# IO_Connector.net
KiCad netlist of a schematic drawn in Altium Designer
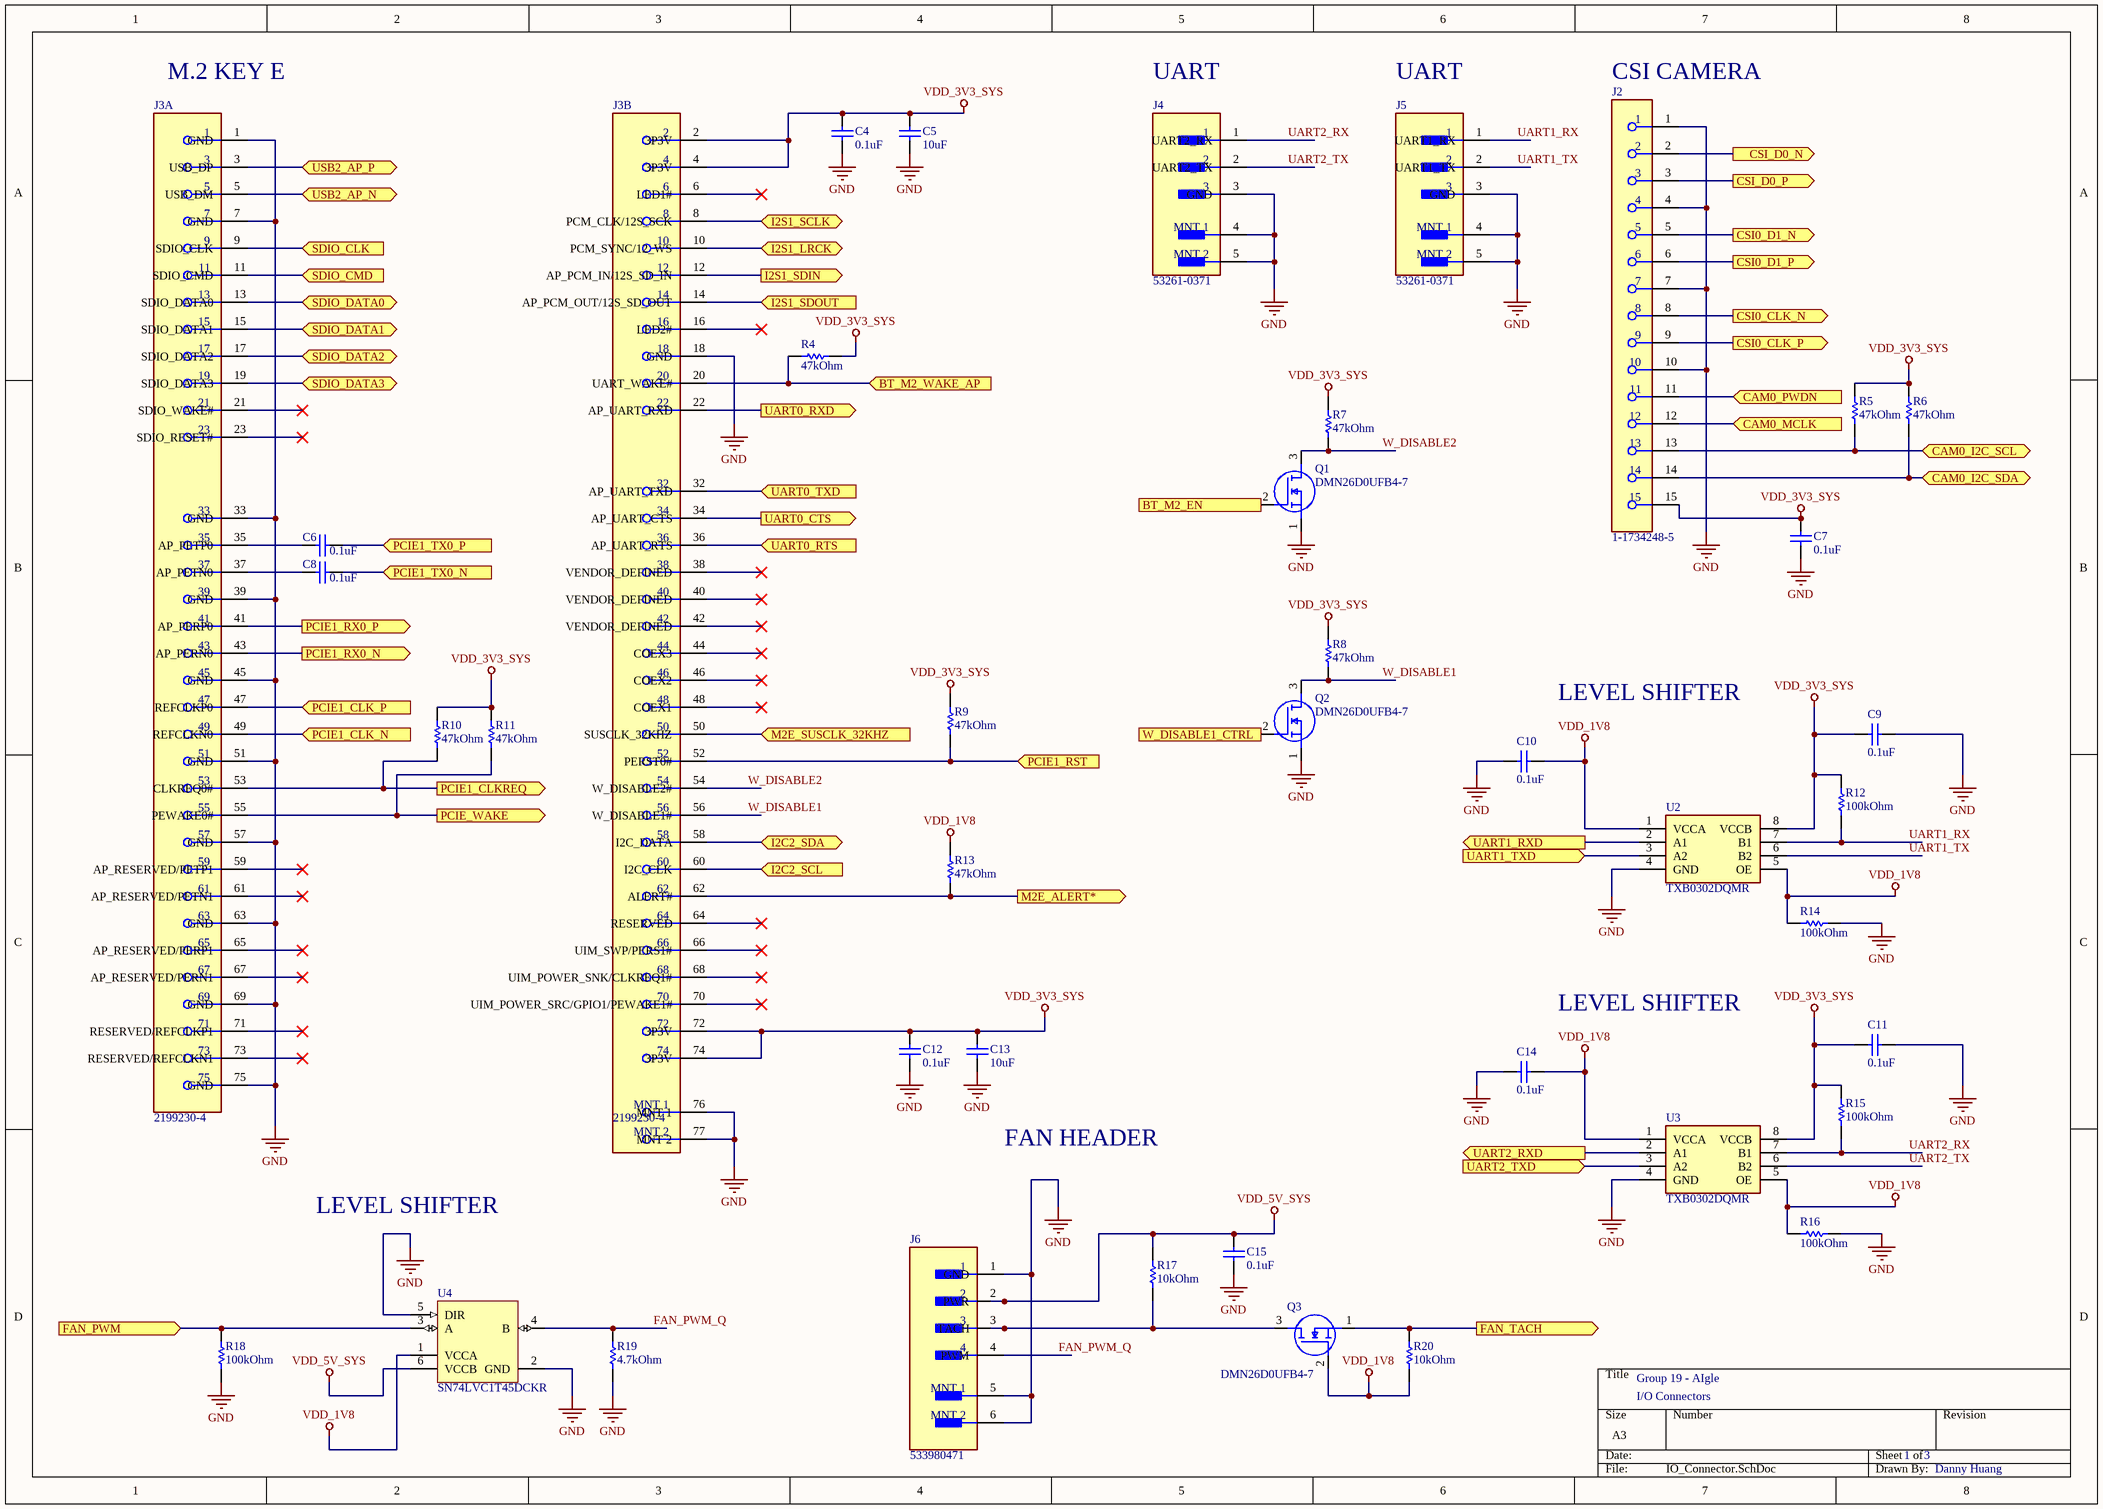
[diagram p0: IO_Connector.SchDoc]

(export (version "E")
  (design (tool "Eeschema 10.0.6"))
  (components
    (comp (ref "C4")
      (value "0.1uF")
      (footprint "CAPC1005X55X30NL05T10")
      (fields (field (name "MANUFACTURER") "Kemet") (field (name "PART NUMBER") "C0402C104K9RACTU"))
      (libsource (lib "Altium Content Vault") (part "CAP"))
    )
    (comp (ref "C5")
      (value "10uF")
      (footprint "CAPC1608X90X35NL10T15")
      (fields (field (name "PART NUMBER") "GRM188R60J106ME47D") (field (name "MANUFACTURER") "Murata"))
      (libsource (lib "Altium Content Vault") (part "CAP"))
    )
    (comp (ref "C6")
      (value "0.1uF")
      (footprint "CAPC1005X55X30NL05T10")
      (fields (field (name "MANUFACTURER") "Kemet") (field (name "PART NUMBER") "C0402C104K9RACTU"))
      (libsource (lib "Altium Content Vault") (part "CAP"))
    )
    (comp (ref "C7")
      (value "0.1uF")
      (footprint "CAPC1005X55X30NL05T10")
      (fields (field (name "MANUFACTURER") "Kemet") (field (name "PART NUMBER") "C0402C104K9RACTU"))
      (libsource (lib "Altium Content Vault") (part "CAP"))
    )
    (comp (ref "C8")
      (value "0.1uF")
      (footprint "CAPC1005X55X30NL05T10")
      (fields (field (name "MANUFACTURER") "Kemet") (field (name "PART NUMBER") "C0402C104K9RACTU"))
      (libsource (lib "Altium Content Vault") (part "CAP"))
    )
    (comp (ref "C9")
      (value "0.1uF")
      (footprint "CAPC1005X55X30NL05T10")
      (fields (field (name "MANUFACTURER") "Kemet") (field (name "PART NUMBER") "C0402C104K9RACTU"))
      (libsource (lib "Altium Content Vault") (part "CAP"))
    )
    (comp (ref "C10")
      (value "0.1uF")
      (footprint "CAPC1005X55X30NL05T10")
      (fields (field (name "MANUFACTURER") "Kemet") (field (name "PART NUMBER") "C0402C104K9RACTU"))
      (libsource (lib "Altium Content Vault") (part "CAP"))
    )
    (comp (ref "C11")
      (value "0.1uF")
      (footprint "CAPC1005X55X30NL05T10")
      (fields (field (name "MANUFACTURER") "Kemet") (field (name "PART NUMBER") "C0402C104K9RACTU"))
      (libsource (lib "Altium Content Vault") (part "CAP"))
    )
    (comp (ref "C12")
      (value "0.1uF")
      (footprint "CAPC1005X55X30NL05T10")
      (fields (field (name "MANUFACTURER") "Kemet") (field (name "PART NUMBER") "C0402C104K9RACTU"))
      (libsource (lib "Altium Content Vault") (part "CAP"))
    )
    (comp (ref "C13")
      (value "10uF")
      (footprint "CAPC1608X90X35NL10T15")
      (fields (field (name "PART NUMBER") "GRM188R60J106ME47D") (field (name "MANUFACTURER") "Murata"))
      (libsource (lib "Altium Content Vault") (part "CAP"))
    )
    (comp (ref "C14")
      (value "0.1uF")
      (footprint "CAPC1005X55X30NL05T10")
      (fields (field (name "MANUFACTURER") "Kemet") (field (name "PART NUMBER") "C0402C104K9RACTU"))
      (libsource (lib "Altium Content Vault") (part "CAP"))
    )
    (comp (ref "C15")
      (value "0.1uF")
      (footprint "CAPC1005X55X30NL05T10")
      (fields (field (name "MANUFACTURER") "Kemet") (field (name "PART NUMBER") "C0402C104K9RACTU"))
      (libsource (lib "Altium Content Vault") (part "CAP"))
    )
    (comp (ref "J2")
      (value "1-1734248-5")
      (footprint "FP-1-1734248-5-MFG")
      (description "CONN FPC VERT 15POS 1.00MM SMD")
      (fields
        (field (name "MANUFACTURER") "TE")
        (field (name "OCTOPART") "https://octopart.com/1-1734248-5-te+connectivity-40620898")
      )
      (libsource (lib "Altium Content Vault") (part "a0777be16b290adccad2a8f9338c195"))
    )
    (comp (ref "J3")
      (value "2199230-4")
      (footprint "FP-2199230-4-MFG")
      (description "CONN FEMALE 67POS 0.020 GOLD")
      (fields
        (field (name "MANUFACTURER") "TE Connectivity")
        (field (name "OCTOPART") "https://octopart.com/2199230-4-te+connectivity-46436156")
      )
      (libsource (lib "Altium Content Vault") (part "6b4bc9aaecd91677fa565b830470f16"))
    )
    (comp (ref "J4")
      (value "53261-0371")
      (footprint "FP-53261-0371-MFG")
      (description "CONN HEADER SMD R/A 3POS 1.25MM")
      (fields
        (field (name "MANUFACTURER") "Molex")
        (field (name "OCTOPART") "https://octopart.com/53261-0371-molex-655314")
      )
      (libsource (lib "Altium Content Vault") (part "13850a6865a90496d8e6d51657cef87"))
    )
    (comp (ref "J5")
      (value "53261-0371")
      (footprint "FP-53261-0371-MFG")
      (description "CONN HEADER SMD R/A 3POS 1.25MM")
      (fields
        (field (name "MANUFACTURER") "Molex")
        (field (name "OCTOPART") "https://octopart.com/53261-0371-molex-655314")
      )
      (libsource (lib "Altium Content Vault") (part "13850a6865a90496d8e6d51657cef87"))
    )
    (comp (ref "J6")
      (value "533980471")
      (footprint "FP-533980471-MFG")
      (description "CONN HEADER SMD 4POS 1.25MM")
      (fields
        (field (name "OCTOPART") "https://octopart.com/53398-0471-molex-655296")
        (field (name "MANUFACTURER") "Molex")
      )
      (libsource (lib "Altium Content Vault") (part "3b6f738a5616415d78381ad43816e4a"))
    )
    (comp (ref "Q1")
      (value "DMN26D0UFB4-7")
      (footprint "SamacSys:DMN26D0UFB47")
      (description "MOSFET (N-Channel)")
      (fields (field (name "MOUSER PART NUMBER") "621-DMN26D0UFB4-7"))
      (libsource (lib "*") (part "DMN26D0UFB4-7"))
    )
    (comp (ref "Q2")
      (value "DMN26D0UFB4-7")
      (footprint "SamacSys:DMN26D0UFB47")
      (description "MOSFET (N-Channel)")
      (fields (field (name "MOUSER PART NUMBER") "621-DMN26D0UFB4-7"))
      (libsource (lib "*") (part "DMN26D0UFB4-7"))
    )
    (comp (ref "Q3")
      (value "DMN26D0UFB4-7")
      (footprint "SamacSys:DMN26D0UFB47")
      (description "MOSFET (N-Channel)")
      (fields (field (name "MOUSER PART NUMBER") "621-DMN26D0UFB4-7"))
      (libsource (lib "*") (part "DMN26D0UFB4-7"))
    )
    (comp (ref "R4")
      (value "47kOhm")
      (footprint "RESC1005X40X25LL05T05")
      (fields (field (name "MANUFACTURER") "Vishay Dale") (field (name "PART NUMBER") "CRCW040247K0JNED"))
      (libsource (lib "Altium Content Vault") (part "RES"))
    )
    (comp (ref "R5")
      (value "47kOhm")
      (footprint "RESC1005X40X25LL05T05")
      (fields (field (name "MANUFACTURER") "Vishay Dale") (field (name "PART NUMBER") "CRCW040247K0JNED"))
      (libsource (lib "Altium Content Vault") (part "RES"))
    )
    (comp (ref "R6")
      (value "47kOhm")
      (footprint "RESC1005X40X25LL05T05")
      (fields (field (name "MANUFACTURER") "Vishay Dale") (field (name "PART NUMBER") "CRCW040247K0JNED"))
      (libsource (lib "Altium Content Vault") (part "RES"))
    )
    (comp (ref "R7")
      (value "47kOhm")
      (footprint "RESC1005X40X25LL05T05")
      (fields (field (name "MANUFACTURER") "Vishay Dale") (field (name "PART NUMBER") "CRCW040247K0JNED"))
      (libsource (lib "Altium Content Vault") (part "RES"))
    )
    (comp (ref "R8")
      (value "47kOhm")
      (footprint "RESC1005X40X25LL05T05")
      (fields (field (name "MANUFACTURER") "Vishay Dale") (field (name "PART NUMBER") "CRCW040247K0JNED"))
      (libsource (lib "Altium Content Vault") (part "RES"))
    )
    (comp (ref "R9")
      (value "47kOhm")
      (footprint "RESC1005X40X25LL05T05")
      (fields (field (name "MANUFACTURER") "Vishay Dale") (field (name "PART NUMBER") "CRCW040247K0JNED"))
      (libsource (lib "Altium Content Vault") (part "RES"))
    )
    (comp (ref "R10")
      (value "47kOhm")
      (footprint "RESC1005X40X25LL05T05")
      (fields (field (name "MANUFACTURER") "Vishay Dale") (field (name "PART NUMBER") "CRCW040247K0JNED"))
      (libsource (lib "Altium Content Vault") (part "RES"))
    )
    (comp (ref "R11")
      (value "47kOhm")
      (footprint "RESC1005X40X25LL05T05")
      (fields (field (name "MANUFACTURER") "Vishay Dale") (field (name "PART NUMBER") "CRCW040247K0JNED"))
      (libsource (lib "Altium Content Vault") (part "RES"))
    )
    (comp (ref "R12")
      (value "100kOhm")
      (footprint "RESC1005X40X25ML05T05")
      (description "Chip Resistor, 100 KOhm, +/- 1%, 0.63 W, -55 to 155 degC, 0402 (1005 Metric), RoHS, Tape and Reel")
      (fields (field (name "TOLERANCE") "1%"))
      (libsource (lib "Altium Content Vault") (part "RES-2"))
    )
    (comp (ref "R13")
      (value "47kOhm")
      (footprint "RESC1005X40X25LL05T05")
      (fields (field (name "MANUFACTURER") "Vishay Dale") (field (name "PART NUMBER") "CRCW040247K0JNED"))
      (libsource (lib "Altium Content Vault") (part "RES"))
    )
    (comp (ref "R14")
      (value "100kOhm")
      (footprint "RESC1005X40X25ML05T05")
      (description "Chip Resistor, 100 KOhm, +/- 1%, 0.63 W, -55 to 155 degC, 0402 (1005 Metric), RoHS, Tape and Reel")
      (fields (field (name "TOLERANCE") "1%"))
      (libsource (lib "Altium Content Vault") (part "RES-2"))
    )
    (comp (ref "R15")
      (value "100kOhm")
      (footprint "RESC1005X40X25ML05T05")
      (description "Chip Resistor, 100 KOhm, +/- 1%, 0.63 W, -55 to 155 degC, 0402 (1005 Metric), RoHS, Tape and Reel")
      (fields (field (name "TOLERANCE") "1%"))
      (libsource (lib "Altium Content Vault") (part "RES-2"))
    )
    (comp (ref "R16")
      (value "100kOhm")
      (footprint "RESC1005X40X25ML05T05")
      (description "Chip Resistor, 100 KOhm, +/- 1%, 0.63 W, -55 to 155 degC, 0402 (1005 Metric), RoHS, Tape and Reel")
      (fields (field (name "TOLERANCE") "1%"))
      (libsource (lib "Altium Content Vault") (part "RES-2"))
    )
    (comp (ref "R17")
      (value "10kOhm")
      (footprint "RESC1005X40X25NL05T05")
      (fields (field (name "MANUFACTURER") "Vishay Dale") (field (name "PART NUMBER") "CRCW040210K0JNED"))
      (libsource (lib "Altium Content Vault") (part "RES"))
    )
    (comp (ref "R18")
      (value "100kOhm")
      (footprint "RESC1005X40X25ML05T05")
      (description "Chip Resistor, 100 KOhm, +/- 1%, 0.63 W, -55 to 155 degC, 0402 (1005 Metric), RoHS, Tape and Reel")
      (fields (field (name "TOLERANCE") "1%"))
      (libsource (lib "Altium Content Vault") (part "RES-2"))
    )
    (comp (ref "R19")
      (value "4.7kOhm")
      (footprint "RESC1005X40X25ML05T05")
      (fields
        (field (name "PART NUMBER") "CRCW04024K70JNED")
        (field (name "MANUFACTURER") "Vishay BCcomponents")
      )
      (libsource (lib "Altium Content Vault") (part "RES"))
    )
    (comp (ref "R20")
      (value "10kOhm")
      (footprint "RESC1005X40X25NL05T05")
      (fields (field (name "MANUFACTURER") "Vishay Dale") (field (name "PART NUMBER") "CRCW040210K0JNED"))
      (libsource (lib "Altium Content Vault") (part "RES"))
    )
    (comp (ref "U2")
      (value "TXB0302DQMR")
      (footprint "SamacSys:SON40P120X180X40-8N")
      (description "Integrated Circuit")
      (fields (field (name "MOUSER PART NUMBER") "595-TXB0302DQMR"))
      (libsource (lib "*") (part "TXB0302DQMR"))
    )
    (comp (ref "U3")
      (value "TXB0302DQMR")
      (footprint "SamacSys:SON40P120X180X40-8N")
      (description "Integrated Circuit")
      (fields (field (name "MOUSER PART NUMBER") "595-TXB0302DQMR"))
      (libsource (lib "*") (part "TXB0302DQMR"))
    )
    (comp (ref "U4")
      (value "SN74LVC1T45DCKR")
      (footprint "DCK0006A_L")
      (fields
        (field (name "MANUFACTURER") "Texas Instruments")
        (field (name "GENERIC PART NUMBER") "SN74LVC1T45")
      )
      (libsource (lib "Altium Content Vault") (part "TI-SN74XVC1T45-6"))
    )
  )
  (nets
    (net (code "1") (name "/BT_M2_EN") (class "Default")
      (node (ref "Q1") (pin "2") (pinfunction "G_2") (pintype "passive"))
    )
    (net (code "2") (name "/BT_M2_WAKE_AP") (class "Default")
      (node (ref "J3") (pin "20") (pinfunction "20_20") (pintype "passive"))
      (node (ref "R4") (pin "2") (pinfunction "2_2") (pintype "passive"))
    )
    (net (code "3") (name "/CAM0_I2C_SCL") (class "Default")
      (node (ref "J2") (pin "13") (pinfunction "13_13") (pintype "passive"))
      (node (ref "R5") (pin "1") (pinfunction "1_1") (pintype "passive"))
    )
    (net (code "4") (name "/CAM0_I2C_SDA") (class "Default")
      (node (ref "J2") (pin "14") (pinfunction "14_14") (pintype "passive"))
      (node (ref "R6") (pin "1") (pinfunction "1_1") (pintype "passive"))
    )
    (net (code "5") (name "/CAM0_MCLK") (class "Default")
      (node (ref "J2") (pin "12") (pinfunction "12_12") (pintype "passive"))
    )
    (net (code "6") (name "/CAM0_PWDN") (class "Default")
      (node (ref "J2") (pin "11") (pinfunction "11_11") (pintype "passive"))
    )
    (net (code "7") (name "/CSI0_CLK_N") (class "Default")
      (node (ref "J2") (pin "8") (pinfunction "8_8") (pintype "passive"))
    )
    (net (code "8") (name "/CSI0_CLK_P") (class "Default")
      (node (ref "J2") (pin "9") (pinfunction "9_9") (pintype "passive"))
    )
    (net (code "9") (name "/CSI0_D1_N") (class "Default")
      (node (ref "J2") (pin "5") (pinfunction "5_5") (pintype "passive"))
    )
    (net (code "10") (name "/CSI0_D1_P") (class "Default")
      (node (ref "J2") (pin "6") (pinfunction "6_6") (pintype "passive"))
    )
    (net (code "11") (name "/CSI_D0_N") (class "Default")
      (node (ref "J2") (pin "2") (pinfunction "2_2") (pintype "passive"))
    )
    (net (code "12") (name "/CSI_D0_P") (class "Default")
      (node (ref "J2") (pin "3") (pinfunction "3_3") (pintype "passive"))
    )
    (net (code "13") (name "/FAN_PWM") (class "Default")
      (node (ref "R18") (pin "1") (pinfunction "1_1") (pintype "passive"))
      (node (ref "U4") (pin "3") (pinfunction "A_3") (pintype "bidirectional"))
    )
    (net (code "14") (name "/FAN_PWM_Q") (class "Default")
      (node (ref "J6") (pin "4") (pinfunction "PWM_4") (pintype "passive"))
      (node (ref "R19") (pin "2") (pinfunction "2_2") (pintype "passive"))
      (node (ref "U4") (pin "4") (pinfunction "B_4") (pintype "bidirectional"))
    )
    (net (code "15") (name "/FAN_TACH") (class "Default")
      (node (ref "Q3") (pin "1") (pinfunction "S_1") (pintype "passive"))
      (node (ref "R20") (pin "2") (pinfunction "2_2") (pintype "passive"))
    )
    (net (code "16") (name "/I2C2_SCL") (class "Default")
      (node (ref "J3") (pin "60") (pinfunction "60_60") (pintype "passive"))
    )
    (net (code "17") (name "/I2C2_SDA") (class "Default")
      (node (ref "J3") (pin "58") (pinfunction "58_58") (pintype "passive"))
    )
    (net (code "18") (name "/I2S1_LRCK") (class "Default")
      (node (ref "J3") (pin "10") (pinfunction "10_10") (pintype "passive"))
    )
    (net (code "19") (name "/I2S1_SCLK") (class "Default")
      (node (ref "J3") (pin "8") (pinfunction "8_8") (pintype "passive"))
    )
    (net (code "20") (name "/I2S1_SDIN") (class "Default")
      (node (ref "J3") (pin "12") (pinfunction "12_12") (pintype "passive"))
    )
    (net (code "21") (name "/I2S1_SDOUT") (class "Default")
      (node (ref "J3") (pin "14") (pinfunction "14_14") (pintype "passive"))
    )
    (net (code "22") (name "/M2E_ALERT*") (class "Default")
      (node (ref "J3") (pin "62") (pinfunction "62_62") (pintype "passive"))
      (node (ref "R13") (pin "1") (pinfunction "1_1") (pintype "passive"))
    )
    (net (code "23") (name "/M2E_SUSCLK_32KHZ") (class "Default")
      (node (ref "J3") (pin "50") (pinfunction "50_50") (pintype "passive"))
    )
    (net (code "24") (name "/PCIE1_CLKREQ") (class "Default")
      (node (ref "J3") (pin "53") (pinfunction "CLKREQ0#_53") (pintype "passive"))
      (node (ref "R10") (pin "1") (pinfunction "1_1") (pintype "passive"))
    )
    (net (code "25") (name "/PCIE1_CLK_N") (class "Default")
      (node (ref "J3") (pin "49") (pinfunction "REFCLKN0_49") (pintype "passive"))
    )
    (net (code "26") (name "/PCIE1_CLK_P") (class "Default")
      (node (ref "J3") (pin "47") (pinfunction "REFCLKP0_47") (pintype "passive"))
    )
    (net (code "27") (name "/PCIE1_RST") (class "Default")
      (node (ref "J3") (pin "52") (pinfunction "52_52") (pintype "passive"))
      (node (ref "R9") (pin "1") (pinfunction "1_1") (pintype "passive"))
    )
    (net (code "28") (name "/PCIE1_RX0_N") (class "Default")
      (node (ref "J3") (pin "43") (pinfunction "AP_PERN0_43") (pintype "passive"))
    )
    (net (code "29") (name "/PCIE1_RX0_P") (class "Default")
      (node (ref "J3") (pin "41") (pinfunction "AP_PERP0_41") (pintype "passive"))
    )
    (net (code "30") (name "/PCIE1_TX0_N") (class "Default")
      (node (ref "C8") (pin "1") (pinfunction "1_1") (pintype "passive"))
    )
    (net (code "31") (name "/PCIE1_TX0_P") (class "Default")
      (node (ref "C6") (pin "1") (pinfunction "1_1") (pintype "passive"))
    )
    (net (code "32") (name "/PCIE_WAKE") (class "Default")
      (node (ref "J3") (pin "55") (pinfunction "PEWAKE0#_55") (pintype "passive"))
      (node (ref "R11") (pin "1") (pinfunction "1_1") (pintype "passive"))
    )
    (net (code "33") (name "/SDIO_CLK") (class "Default")
      (node (ref "J3") (pin "9") (pinfunction "SDIO_CLK_9") (pintype "passive"))
    )
    (net (code "34") (name "/SDIO_CMD") (class "Default")
      (node (ref "J3") (pin "11") (pinfunction "SDIO_CMD_11") (pintype "passive"))
    )
    (net (code "35") (name "/SDIO_DATA0") (class "Default")
      (node (ref "J3") (pin "13") (pinfunction "SDIO_DATA0_13") (pintype "passive"))
    )
    (net (code "36") (name "/SDIO_DATA1") (class "Default")
      (node (ref "J3") (pin "15") (pinfunction "SDIO_DATA1_15") (pintype "passive"))
    )
    (net (code "37") (name "/SDIO_DATA2") (class "Default")
      (node (ref "J3") (pin "17") (pinfunction "SDIO_DATA2_17") (pintype "passive"))
    )
    (net (code "38") (name "/SDIO_DATA3") (class "Default")
      (node (ref "J3") (pin "19") (pinfunction "SDIO_DATA3_19") (pintype "passive"))
    )
    (net (code "39") (name "/UART0_CTS") (class "Default")
      (node (ref "J3") (pin "34") (pinfunction "34_34") (pintype "passive"))
    )
    (net (code "40") (name "/UART0_RTS") (class "Default")
      (node (ref "J3") (pin "36") (pinfunction "36_36") (pintype "passive"))
    )
    (net (code "41") (name "/UART0_RXD") (class "Default")
      (node (ref "J3") (pin "22") (pinfunction "22_22") (pintype "passive"))
    )
    (net (code "42") (name "/UART0_TXD") (class "Default")
      (node (ref "J3") (pin "32") (pinfunction "32_32") (pintype "passive"))
    )
    (net (code "43") (name "/UART1_RX") (class "Default")
      (node (ref "J5") (pin "1") (pinfunction "UART2_RX_1") (pintype "passive"))
      (node (ref "R12") (pin "1") (pinfunction "1_1") (pintype "passive"))
      (node (ref "U2") (pin "7") (pinfunction "B1_7") (pintype "passive"))
    )
    (net (code "44") (name "/UART1_RXD") (class "Default")
      (node (ref "U2") (pin "2") (pinfunction "A1_2") (pintype "passive"))
    )
    (net (code "45") (name "/UART1_TX") (class "Default")
      (node (ref "J5") (pin "2") (pinfunction "UART2_TX_2") (pintype "passive"))
      (node (ref "U2") (pin "6") (pinfunction "B2_6") (pintype "passive"))
    )
    (net (code "46") (name "/UART1_TXD") (class "Default")
      (node (ref "U2") (pin "3") (pinfunction "A2_3") (pintype "passive"))
    )
    (net (code "47") (name "/UART2_RX") (class "Default")
      (node (ref "J4") (pin "1") (pinfunction "UART2_RX_1") (pintype "passive"))
      (node (ref "R15") (pin "1") (pinfunction "1_1") (pintype "passive"))
      (node (ref "U3") (pin "7") (pinfunction "B1_7") (pintype "passive"))
    )
    (net (code "48") (name "/UART2_RXD") (class "Default")
      (node (ref "U3") (pin "2") (pinfunction "A1_2") (pintype "passive"))
    )
    (net (code "49") (name "/UART2_TX") (class "Default")
      (node (ref "J4") (pin "2") (pinfunction "UART2_TX_2") (pintype "passive"))
      (node (ref "U3") (pin "6") (pinfunction "B2_6") (pintype "passive"))
    )
    (net (code "50") (name "/UART2_TXD") (class "Default")
      (node (ref "U3") (pin "3") (pinfunction "A2_3") (pintype "passive"))
    )
    (net (code "51") (name "/USB2_AP_N") (class "Default")
      (node (ref "J3") (pin "5") (pinfunction "USB_DM_5") (pintype "passive"))
    )
    (net (code "52") (name "/USB2_AP_P") (class "Default")
      (node (ref "J3") (pin "3") (pinfunction "USB_DP_3") (pintype "passive"))
    )
    (net (code "53") (name "/W_DISABLE1") (class "Default")
      (node (ref "J3") (pin "56") (pinfunction "56_56") (pintype "passive"))
      (node (ref "Q2") (pin "3") (pinfunction "D_3") (pintype "passive"))
      (node (ref "R8") (pin "1") (pinfunction "1_1") (pintype "passive"))
    )
    (net (code "54") (name "/W_DISABLE1_CTRL") (class "Default")
      (node (ref "Q2") (pin "2") (pinfunction "G_2") (pintype "passive"))
    )
    (net (code "55") (name "/W_DISABLE2") (class "Default")
      (node (ref "J3") (pin "54") (pinfunction "54_54") (pintype "passive"))
      (node (ref "Q1") (pin "3") (pinfunction "D_3") (pintype "passive"))
      (node (ref "R7") (pin "1") (pinfunction "1_1") (pintype "passive"))
    )
    (net (code "56") (name "GND") (class "Default")
      (node (ref "C10") (pin "2") (pinfunction "2_2") (pintype "passive"))
      (node (ref "C11") (pin "1") (pinfunction "1_1") (pintype "passive"))
      (node (ref "C12") (pin "1") (pinfunction "1_1") (pintype "passive"))
      (node (ref "C13") (pin "1") (pinfunction "1_1") (pintype "passive"))
      (node (ref "C14") (pin "2") (pinfunction "2_2") (pintype "passive"))
      (node (ref "C15") (pin "2") (pinfunction "2_2") (pintype "passive"))
      (node (ref "C4") (pin "1") (pinfunction "1_1") (pintype "passive"))
      (node (ref "C5") (pin "1") (pinfunction "1_1") (pintype "passive"))
      (node (ref "C7") (pin "1") (pinfunction "1_1") (pintype "passive"))
      (node (ref "C9") (pin "1") (pinfunction "1_1") (pintype "passive"))
      (node (ref "J2") (pin "1") (pinfunction "1_1") (pintype "passive"))
      (node (ref "J2") (pin "10") (pinfunction "10_10") (pintype "passive"))
      (node (ref "J2") (pin "4") (pinfunction "4_4") (pintype "passive"))
      (node (ref "J2") (pin "7") (pinfunction "7_7") (pintype "passive"))
      (node (ref "J3") (pin "1") (pinfunction "GND_1") (pintype "passive"))
      (node (ref "J3") (pin "18") (pinfunction "18_18") (pintype "passive"))
      (node (ref "J3") (pin "33") (pinfunction "GND_33") (pintype "passive"))
      (node (ref "J3") (pin "39") (pinfunction "GND_39") (pintype "passive"))
      (node (ref "J3") (pin "45") (pinfunction "GND_45") (pintype "passive"))
      (node (ref "J3") (pin "51") (pinfunction "GND_51") (pintype "passive"))
      (node (ref "J3") (pin "57") (pinfunction "GND_57") (pintype "passive"))
      (node (ref "J3") (pin "63") (pinfunction "GND_63") (pintype "passive"))
      (node (ref "J3") (pin "69") (pinfunction "GND_69") (pintype "passive"))
      (node (ref "J3") (pin "7") (pinfunction "GND_7") (pintype "passive"))
      (node (ref "J3") (pin "75") (pinfunction "GND_75") (pintype "passive"))
      (node (ref "J3") (pin "76") (pinfunction "MNT_1_76") (pintype "passive"))
      (node (ref "J3") (pin "77") (pinfunction "MNT_2_77") (pintype "passive"))
      (node (ref "J4") (pin "3") (pinfunction "GND_3") (pintype "passive"))
      (node (ref "J4") (pin "4") (pinfunction "MNT_1_4") (pintype "passive"))
      (node (ref "J4") (pin "5") (pinfunction "MNT_2_5") (pintype "passive"))
      (node (ref "J5") (pin "3") (pinfunction "GND_3") (pintype "passive"))
      (node (ref "J5") (pin "4") (pinfunction "MNT_1_4") (pintype "passive"))
      (node (ref "J5") (pin "5") (pinfunction "MNT_2_5") (pintype "passive"))
      (node (ref "J6") (pin "1") (pinfunction "GND_1") (pintype "passive"))
      (node (ref "J6") (pin "5") (pinfunction "MNT_1_5") (pintype "passive"))
      (node (ref "J6") (pin "6") (pinfunction "MNT_2_6") (pintype "passive"))
      (node (ref "Q1") (pin "1") (pinfunction "S_1") (pintype "passive"))
      (node (ref "Q2") (pin "1") (pinfunction "S_1") (pintype "passive"))
      (node (ref "R14") (pin "1") (pinfunction "1_1") (pintype "passive"))
      (node (ref "R16") (pin "1") (pinfunction "1_1") (pintype "passive"))
      (node (ref "R18") (pin "2") (pinfunction "2_2") (pintype "passive"))
      (node (ref "R19") (pin "1") (pinfunction "1_1") (pintype "passive"))
      (node (ref "U2") (pin "4") (pinfunction "GND_4") (pintype "passive"))
      (node (ref "U3") (pin "4") (pinfunction "GND_4") (pintype "passive"))
      (node (ref "U4") (pin "2") (pinfunction "GND_2") (pintype "power_in"))
      (node (ref "U4") (pin "5") (pinfunction "DIR_5") (pintype "input"))
    )
    (net (code "57") (name "Net-(J3A-AP_PETN0)") (class "Default")
      (node (ref "C8") (pin "2") (pinfunction "2_2") (pintype "passive"))
      (node (ref "J3") (pin "37") (pinfunction "AP_PETN0_37") (pintype "passive"))
    )
    (net (code "58") (name "Net-(J3A-AP_PETP0)") (class "Default")
      (node (ref "C6") (pin "2") (pinfunction "2_2") (pintype "passive"))
      (node (ref "J3") (pin "35") (pinfunction "AP_PETP0_35") (pintype "passive"))
    )
    (net (code "59") (name "Net-(J6-TACH)") (class "Default")
      (node (ref "J6") (pin "3") (pinfunction "TACH_3") (pintype "passive"))
      (node (ref "Q3") (pin "3") (pinfunction "D_3") (pintype "passive"))
      (node (ref "R17") (pin "1") (pinfunction "1_1") (pintype "passive"))
    )
    (net (code "60") (name "VDD_1V8") (class "Default")
      (node (ref "C10") (pin "1") (pinfunction "1_1") (pintype "passive"))
      (node (ref "C14") (pin "1") (pinfunction "1_1") (pintype "passive"))
      (node (ref "Q3") (pin "2") (pinfunction "G_2") (pintype "passive"))
      (node (ref "R13") (pin "2") (pinfunction "2_2") (pintype "passive"))
      (node (ref "R14") (pin "2") (pinfunction "2_2") (pintype "passive"))
      (node (ref "R16") (pin "2") (pinfunction "2_2") (pintype "passive"))
      (node (ref "R20") (pin "1") (pinfunction "1_1") (pintype "passive"))
      (node (ref "U2") (pin "1") (pinfunction "VCCA_1") (pintype "passive"))
      (node (ref "U2") (pin "5") (pinfunction "OE_5") (pintype "passive"))
      (node (ref "U3") (pin "1") (pinfunction "VCCA_1") (pintype "passive"))
      (node (ref "U3") (pin "5") (pinfunction "OE_5") (pintype "passive"))
      (node (ref "U4") (pin "1") (pinfunction "VCCA_1") (pintype "power_in"))
    )
    (net (code "61") (name "VDD_3V3_SYS") (class "Default")
      (node (ref "C11") (pin "2") (pinfunction "2_2") (pintype "passive"))
      (node (ref "C12") (pin "2") (pinfunction "2_2") (pintype "passive"))
      (node (ref "C13") (pin "2") (pinfunction "2_2") (pintype "passive"))
      (node (ref "C4") (pin "2") (pinfunction "2_2") (pintype "passive"))
      (node (ref "C5") (pin "2") (pinfunction "2_2") (pintype "passive"))
      (node (ref "C7") (pin "2") (pinfunction "2_2") (pintype "passive"))
      (node (ref "C9") (pin "2") (pinfunction "2_2") (pintype "passive"))
      (node (ref "J2") (pin "15") (pinfunction "15_15") (pintype "passive"))
      (node (ref "J3") (pin "2") (pinfunction "2_2") (pintype "passive"))
      (node (ref "J3") (pin "4") (pinfunction "4_4") (pintype "passive"))
      (node (ref "J3") (pin "72") (pinfunction "72_72") (pintype "passive"))
      (node (ref "J3") (pin "74") (pinfunction "74_74") (pintype "passive"))
      (node (ref "R10") (pin "2") (pinfunction "2_2") (pintype "passive"))
      (node (ref "R11") (pin "2") (pinfunction "2_2") (pintype "passive"))
      (node (ref "R12") (pin "2") (pinfunction "2_2") (pintype "passive"))
      (node (ref "R15") (pin "2") (pinfunction "2_2") (pintype "passive"))
      (node (ref "R4") (pin "1") (pinfunction "1_1") (pintype "passive"))
      (node (ref "R5") (pin "2") (pinfunction "2_2") (pintype "passive"))
      (node (ref "R6") (pin "2") (pinfunction "2_2") (pintype "passive"))
      (node (ref "R7") (pin "2") (pinfunction "2_2") (pintype "passive"))
      (node (ref "R8") (pin "2") (pinfunction "2_2") (pintype "passive"))
      (node (ref "R9") (pin "2") (pinfunction "2_2") (pintype "passive"))
      (node (ref "U2") (pin "8") (pinfunction "VCCB_8") (pintype "passive"))
      (node (ref "U3") (pin "8") (pinfunction "VCCB_8") (pintype "passive"))
    )
    (net (code "62") (name "VDD_5V_SYS") (class "Default")
      (node (ref "C15") (pin "1") (pinfunction "1_1") (pintype "passive"))
      (node (ref "J6") (pin "2") (pinfunction "PWR_2") (pintype "passive"))
      (node (ref "R17") (pin "2") (pinfunction "2_2") (pintype "passive"))
      (node (ref "U4") (pin "6") (pinfunction "VCCB_6") (pintype "power_in"))
    )
    (net (code "63") (name "unconnected-(J3-Pad6)") (class "Default")
      (node (ref "J3") (pin "6") (pinfunction "6_6") (pintype "passive+no_connect"))
    )
    (net (code "64") (name "unconnected-(J3-Pad16)") (class "Default")
      (node (ref "J3") (pin "16") (pinfunction "16_16") (pintype "passive+no_connect"))
    )
    (net (code "65") (name "unconnected-(J3-Pad38)") (class "Default")
      (node (ref "J3") (pin "38") (pinfunction "38_38") (pintype "passive+no_connect"))
    )
    (net (code "66") (name "unconnected-(J3-Pad40)") (class "Default")
      (node (ref "J3") (pin "40") (pinfunction "40_40") (pintype "passive+no_connect"))
    )
    (net (code "67") (name "unconnected-(J3-Pad42)") (class "Default")
      (node (ref "J3") (pin "42") (pinfunction "42_42") (pintype "passive+no_connect"))
    )
    (net (code "68") (name "unconnected-(J3-Pad44)") (class "Default")
      (node (ref "J3") (pin "44") (pinfunction "44_44") (pintype "passive+no_connect"))
    )
    (net (code "69") (name "unconnected-(J3-Pad46)") (class "Default")
      (node (ref "J3") (pin "46") (pinfunction "46_46") (pintype "passive+no_connect"))
    )
    (net (code "70") (name "unconnected-(J3-Pad48)") (class "Default")
      (node (ref "J3") (pin "48") (pinfunction "48_48") (pintype "passive+no_connect"))
    )
    (net (code "71") (name "unconnected-(J3-Pad64)") (class "Default")
      (node (ref "J3") (pin "64") (pinfunction "64_64") (pintype "passive+no_connect"))
    )
    (net (code "72") (name "unconnected-(J3-Pad66)") (class "Default")
      (node (ref "J3") (pin "66") (pinfunction "66_66") (pintype "passive+no_connect"))
    )
    (net (code "73") (name "unconnected-(J3-Pad68)") (class "Default")
      (node (ref "J3") (pin "68") (pinfunction "68_68") (pintype "passive+no_connect"))
    )
    (net (code "74") (name "unconnected-(J3-Pad70)") (class "Default")
      (node (ref "J3") (pin "70") (pinfunction "70_70") (pintype "passive+no_connect"))
    )
    (net (code "75") (name "unconnected-(J3A-AP_RESERVED{slash}PERN1-Pad67)") (class "Default")
      (node (ref "J3") (pin "67") (pinfunction "AP_RESERVED/PERN1_67") (pintype "passive+no_connect"))
    )
    (net (code "76") (name "unconnected-(J3A-AP_RESERVED{slash}PERP1-Pad65)") (class "Default")
      (node (ref "J3") (pin "65") (pinfunction "AP_RESERVED/PERP1_65") (pintype "passive+no_connect"))
    )
    (net (code "77") (name "unconnected-(J3A-AP_RESERVED{slash}PETN1-Pad61)") (class "Default")
      (node (ref "J3") (pin "61") (pinfunction "AP_RESERVED/PETN1_61") (pintype "passive+no_connect"))
    )
    (net (code "78") (name "unconnected-(J3A-AP_RESERVED{slash}PETP1-Pad59)") (class "Default")
      (node (ref "J3") (pin "59") (pinfunction "AP_RESERVED/PETP1_59") (pintype "passive+no_connect"))
    )
    (net (code "79") (name "unconnected-(J3A-RESERVED{slash}REFCLKN1-Pad73)") (class "Default")
      (node (ref "J3") (pin "73") (pinfunction "RESERVED/REFCLKN1_73") (pintype "passive+no_connect"))
    )
    (net (code "80") (name "unconnected-(J3A-RESERVED{slash}REFCLKP1-Pad71)") (class "Default")
      (node (ref "J3") (pin "71") (pinfunction "RESERVED/REFCLKP1_71") (pintype "passive+no_connect"))
    )
    (net (code "81") (name "unconnected-(J3A-SDIO_RESET#-Pad23)") (class "Default")
      (node (ref "J3") (pin "23") (pinfunction "SDIO_RESET#_23") (pintype "passive+no_connect"))
    )
    (net (code "82") (name "unconnected-(J3A-SDIO_WAKE#-Pad21)") (class "Default")
      (node (ref "J3") (pin "21") (pinfunction "SDIO_WAKE#_21") (pintype "passive+no_connect"))
    )
  )
)
